# gcb95_redraw.net
KiCad netlist of a schematic drawn in EAGLE
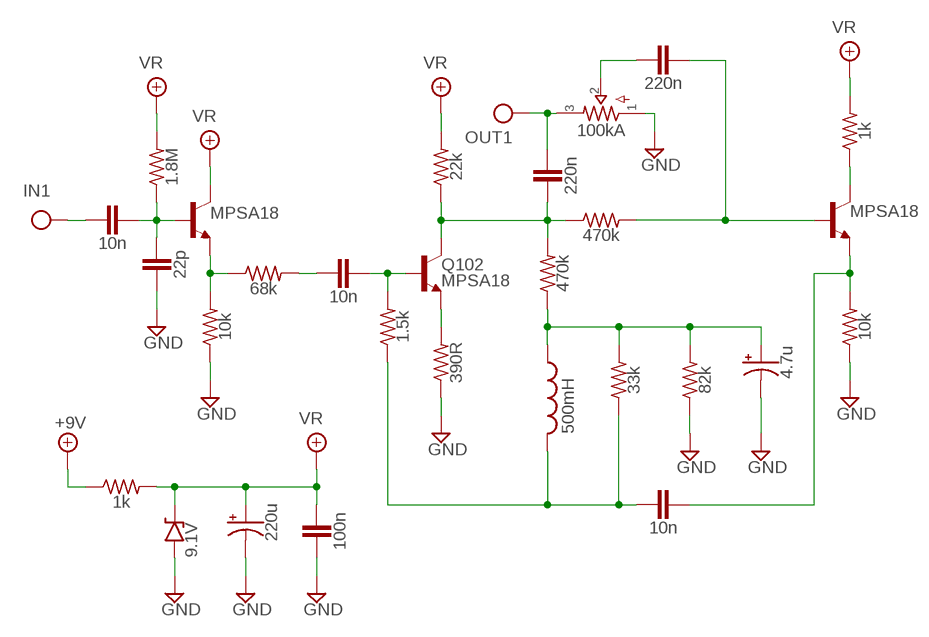
[diagram p0: schematic, sheet 1]

(export (version "E")
  (design (tool "Eeschema 10.0.6"))
  (components
    (comp (ref "C101")
      (value "220u")
      (footprint "eagle-import:050_020")
      (libsource (lib "eagle-import") (part "0500"))
    )
    (comp (ref "C102")
      (value "100n")
      (footprint "eagle-import:050X030_025")
      (libsource (lib "eagle-import") (part "CER/FILM1"))
    )
    (comp (ref "C103")
      (value "10n")
      (footprint "eagle-import:BOX_SMALL")
      (libsource (lib "eagle-import") (part "CER/FILMBOX.1"))
    )
    (comp (ref "C104")
      (value "22p")
      (footprint "eagle-import:050X030_025")
      (libsource (lib "eagle-import") (part "CER/FILM1"))
    )
    (comp (ref "C105")
      (value "10n")
      (footprint "eagle-import:BOX_SMALL")
      (libsource (lib "eagle-import") (part "CER/FILMBOX.1"))
    )
    (comp (ref "C106")
      (value "220n")
      (footprint "eagle-import:050X030_025")
      (libsource (lib "eagle-import") (part "CER/FILM1"))
    )
    (comp (ref "C107")
      (value "220n")
      (footprint "eagle-import:BOX_SMALL")
      (libsource (lib "eagle-import") (part "CER/FILMBOX.1"))
    )
    (comp (ref "C108")
      (value "10n")
      (footprint "eagle-import:BOX_SMALL")
      (libsource (lib "eagle-import") (part "CER/FILMBOX.1"))
    )
    (comp (ref "C109")
      (value "4.7u")
      (footprint "eagle-import:050_020")
      (libsource (lib "eagle-import") (part "0500"))
    )
    (comp (ref "D1")
      (value "9.1V")
      (footprint "eagle-import:DO41-2")
      (libsource (lib "eagle-import") (part "ZENER.2"))
    )
    (comp (ref "L101")
      (value "500mH")
      (footprint "eagle-import:WAH")
      (libsource (lib "eagle-import") (part "WAH"))
    )
    (comp (ref "POT101")
      (value "100kA")
      (footprint "eagle-import:16MM")
      (libsource (lib "eagle-import") (part "POTS16MM"))
    )
    (comp (ref "Q101")
      (value "MPSA18")
      (footprint "eagle-import:TO92-")
      (libsource (lib "eagle-import") (part "MPSA18"))
    )
    (comp (ref "Q102")
      (value "MPSA18")
      (footprint "eagle-import:TO92-")
      (libsource (lib "eagle-import") (part "MPSA18"))
    )
    (comp (ref "Q103")
      (value "MPSA18")
      (footprint "eagle-import:TO92-")
      (libsource (lib "eagle-import") (part "MPSA18"))
    )
    (comp (ref "R1")
      (value "1k")
      (footprint "eagle-import:R0207_3")
      (libsource (lib "eagle-import") (part "R_.3B"))
    )
    (comp (ref "R102")
      (value "1.8M")
      (footprint "eagle-import:R0207_3")
      (libsource (lib "eagle-import") (part "R_.3B"))
    )
    (comp (ref "R103")
      (value "10k")
      (footprint "eagle-import:R0207_3")
      (libsource (lib "eagle-import") (part "R_.3B"))
    )
    (comp (ref "R104")
      (value "68k")
      (footprint "eagle-import:R0207_3")
      (libsource (lib "eagle-import") (part "R_.3B"))
    )
    (comp (ref "R105")
      (value "1.5k")
      (footprint "eagle-import:R0207_3")
      (libsource (lib "eagle-import") (part "R_.3B"))
    )
    (comp (ref "R106")
      (value "22k")
      (footprint "eagle-import:R0207_3")
      (libsource (lib "eagle-import") (part "R_.3B"))
    )
    (comp (ref "R107")
      (value "390R")
      (footprint "eagle-import:R0207_3")
      (libsource (lib "eagle-import") (part "R_.3B"))
    )
    (comp (ref "R108")
      (value "470k")
      (footprint "eagle-import:R0207_3")
      (libsource (lib "eagle-import") (part "R_.3B"))
    )
    (comp (ref "R110")
      (value "470k")
      (footprint "eagle-import:R0207_3")
      (libsource (lib "eagle-import") (part "R_.3B"))
    )
    (comp (ref "R111")
      (value "33k")
      (footprint "eagle-import:R0207_3")
      (libsource (lib "eagle-import") (part "R_.3B"))
    )
    (comp (ref "R112")
      (value "82k")
      (footprint "eagle-import:R0207_3")
      (libsource (lib "eagle-import") (part "R_.3B"))
    )
    (comp (ref "R113")
      (value "1k")
      (footprint "eagle-import:R0207_3")
      (libsource (lib "eagle-import") (part "R_.3B"))
    )
    (comp (ref "R114")
      (value "10k")
      (footprint "eagle-import:R0207_3")
      (libsource (lib "eagle-import") (part "R_.3B"))
    )
  )
  (nets
    (net (code "1") (name "+9V") (class "Default")
      (node (ref "R1") (pin "1") (pinfunction "1_1") (pintype "passive"))
    )
    (net (code "2") (name "GND") (class "Default")
      (node (ref "C101") (pin "-") (pinfunction "-_-") (pintype "passive"))
      (node (ref "C102") (pin "2") (pinfunction "2_2") (pintype "passive"))
      (node (ref "C104") (pin "2") (pinfunction "2_2") (pintype "passive"))
      (node (ref "C109") (pin "-") (pinfunction "-_-") (pintype "passive"))
      (node (ref "D1") (pin "A") (pinfunction "A_A") (pintype "passive"))
      (node (ref "POT101") (pin "1") (pinfunction "1_1") (pintype "passive"))
      (node (ref "R103") (pin "1") (pinfunction "1_1") (pintype "passive"))
      (node (ref "R107") (pin "1") (pinfunction "1_1") (pintype "passive"))
      (node (ref "R112") (pin "1") (pinfunction "1_1") (pintype "passive"))
      (node (ref "R114") (pin "1") (pinfunction "1_1") (pintype "passive"))
    )
    (net (code "3") (name "IN") (class "Default")
      (node (ref "C103") (pin "2") (pinfunction "2_2") (pintype "passive"))
    )
    (net (code "4") (name "Net-(C105-Pad2)") (class "Default")
      (node (ref "C105") (pin "2") (pinfunction "2_2") (pintype "passive"))
      (node (ref "R104") (pin "2") (pinfunction "2_2") (pintype "passive"))
    )
    (net (code "5") (name "Net-(C107-Pad2)") (class "Default")
      (node (ref "C107") (pin "2") (pinfunction "2_2") (pintype "passive"))
      (node (ref "POT101") (pin "2") (pinfunction "2_2") (pintype "passive"))
    )
    (net (code "6") (name "Net-(C108-Pad2)") (class "Default")
      (node (ref "C108") (pin "2") (pinfunction "2_2") (pintype "passive"))
      (node (ref "L101") (pin "2") (pinfunction "2_2") (pintype "passive"))
      (node (ref "R105") (pin "1") (pinfunction "1_1") (pintype "passive"))
      (node (ref "R111") (pin "1") (pinfunction "1_1") (pintype "passive"))
    )
    (net (code "7") (name "Net-(C109-Pad+)") (class "Default")
      (node (ref "C109") (pin "+") (pinfunction "+_+") (pintype "passive"))
      (node (ref "L101") (pin "1") (pinfunction "1_1") (pintype "passive"))
      (node (ref "R108") (pin "1") (pinfunction "1_1") (pintype "passive"))
      (node (ref "R111") (pin "2") (pinfunction "2_2") (pintype "passive"))
      (node (ref "R112") (pin "2") (pinfunction "2_2") (pintype "passive"))
    )
    (net (code "8") (name "Net-(Q101-B)") (class "Default")
      (node (ref "C103") (pin "1") (pinfunction "1_1") (pintype "passive"))
      (node (ref "C104") (pin "1") (pinfunction "1_1") (pintype "passive"))
      (node (ref "Q101") (pin "2") (pinfunction "B_2") (pintype "passive"))
      (node (ref "R102") (pin "1") (pinfunction "1_1") (pintype "passive"))
    )
    (net (code "9") (name "Net-(Q101-E)") (class "Default")
      (node (ref "Q101") (pin "3") (pinfunction "E_3") (pintype "passive"))
      (node (ref "R103") (pin "2") (pinfunction "2_2") (pintype "passive"))
      (node (ref "R104") (pin "1") (pinfunction "1_1") (pintype "passive"))
    )
    (net (code "10") (name "Net-(Q102-B)") (class "Default")
      (node (ref "C105") (pin "1") (pinfunction "1_1") (pintype "passive"))
      (node (ref "Q102") (pin "2") (pinfunction "B_2") (pintype "passive"))
      (node (ref "R105") (pin "2") (pinfunction "2_2") (pintype "passive"))
    )
    (net (code "11") (name "Net-(Q102-C)") (class "Default")
      (node (ref "C106") (pin "2") (pinfunction "2_2") (pintype "passive"))
      (node (ref "Q102") (pin "1") (pinfunction "C_1") (pintype "passive"))
      (node (ref "R106") (pin "1") (pinfunction "1_1") (pintype "passive"))
      (node (ref "R108") (pin "2") (pinfunction "2_2") (pintype "passive"))
      (node (ref "R110") (pin "1") (pinfunction "1_1") (pintype "passive"))
    )
    (net (code "12") (name "Net-(Q102-E)") (class "Default")
      (node (ref "Q102") (pin "3") (pinfunction "E_3") (pintype "passive"))
      (node (ref "R107") (pin "2") (pinfunction "2_2") (pintype "passive"))
    )
    (net (code "13") (name "Net-(Q103-B)") (class "Default")
      (node (ref "C107") (pin "1") (pinfunction "1_1") (pintype "passive"))
      (node (ref "Q103") (pin "2") (pinfunction "B_2") (pintype "passive"))
      (node (ref "R110") (pin "2") (pinfunction "2_2") (pintype "passive"))
    )
    (net (code "14") (name "Net-(Q103-C)") (class "Default")
      (node (ref "Q103") (pin "1") (pinfunction "C_1") (pintype "passive"))
      (node (ref "R113") (pin "1") (pinfunction "1_1") (pintype "passive"))
    )
    (net (code "15") (name "Net-(Q103-E)") (class "Default")
      (node (ref "C108") (pin "1") (pinfunction "1_1") (pintype "passive"))
      (node (ref "Q103") (pin "3") (pinfunction "E_3") (pintype "passive"))
      (node (ref "R114") (pin "2") (pinfunction "2_2") (pintype "passive"))
    )
    (net (code "16") (name "OUT") (class "Default")
      (node (ref "C106") (pin "1") (pinfunction "1_1") (pintype "passive"))
      (node (ref "POT101") (pin "3") (pinfunction "3_3") (pintype "passive"))
    )
    (net (code "17") (name "VR") (class "Default")
      (node (ref "C101") (pin "+") (pinfunction "+_+") (pintype "passive"))
      (node (ref "C102") (pin "1") (pinfunction "1_1") (pintype "passive"))
      (node (ref "D1") (pin "C") (pinfunction "C_C") (pintype "passive"))
      (node (ref "Q101") (pin "1") (pinfunction "C_1") (pintype "passive"))
      (node (ref "R1") (pin "2") (pinfunction "2_2") (pintype "passive"))
      (node (ref "R102") (pin "2") (pinfunction "2_2") (pintype "passive"))
      (node (ref "R106") (pin "2") (pinfunction "2_2") (pintype "passive"))
      (node (ref "R113") (pin "2") (pinfunction "2_2") (pintype "passive"))
    )
  )
)
